# EL_Inverter1.net
KiCad netlist of a schematic drawn in EAGLE
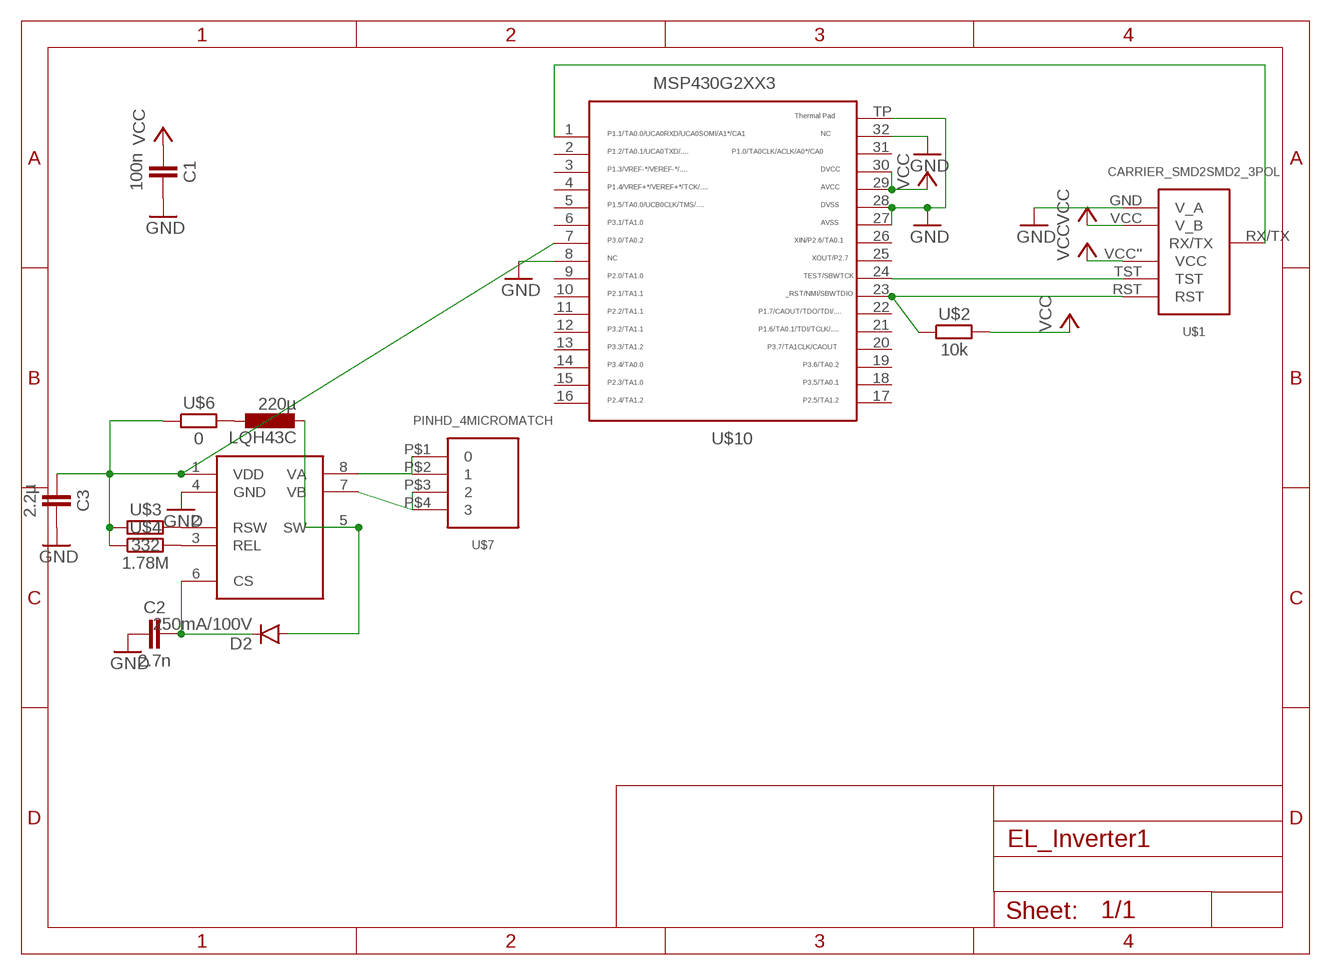
[diagram p0: schematic, sheet 1]

(export (version "E")
  (design (tool "Eeschema 10.0.6"))
  (components
    (comp (ref "C1")
      (value "100n")
      (footprint "eagle-import:603")
      (libsource (lib "eagle-import") (part "CAPACITOR"))
    )
    (comp (ref "C2")
      (value "2.7n")
      (footprint "eagle-import:603")
      (libsource (lib "eagle-import") (part "CAPACITOR"))
    )
    (comp (ref "C3")
      (value "2.2µ")
      (footprint "eagle-import:603")
      (libsource (lib "eagle-import") (part "CAPACITOR"))
    )
    (comp (ref "D2")
      (value "250mA/100V")
      (footprint "eagle-import:SOD-323")
      (libsource (lib "eagle-import") (part "DIODEBAS16"))
    )
    (comp (ref "LQH43C")
      (value "220µ")
      (footprint "eagle-import:L1812")
      (libsource (lib "eagle-import") (part "L-EUL1812"))
    )
    (comp (ref "U$1")
      (value "CARRIER_SMD2SMD2_3POL")
      (footprint "eagle-import:CARRIER_SMD2_3POL")
      (libsource (lib "eagle-import") (part "CARRIER_SMD2SMD2_3POL"))
    )
    (comp (ref "U$2")
      (value "10k")
      (footprint "eagle-import:603")
      (libsource (lib "eagle-import") (part "RESISTOR0603"))
    )
    (comp (ref "U$3")
      (value "332")
      (footprint "eagle-import:603")
      (libsource (lib "eagle-import") (part "RESISTOR0603"))
    )
    (comp (ref "U$4")
      (value "1.78M")
      (footprint "eagle-import:603")
      (libsource (lib "eagle-import") (part "RESISTOR0603"))
    )
    (comp (ref "U$6")
      (value "0")
      (footprint "eagle-import:603")
      (libsource (lib "eagle-import") (part "RESISTOR0603"))
    )
    (comp (ref "U$7")
      (value "PINHD_4MICROMATCH")
      (footprint "eagle-import:MICROMATCH4P0L")
      (libsource (lib "eagle-import") (part "PINHD_4MICROMATCH"))
    )
    (comp (ref "U$8")
      (value "MIC4830")
      (footprint "eagle-import:MSOP8")
      (libsource (lib "eagle-import") (part "MIC4830"))
    )
    (comp (ref "U$10")
      (value "MSP430G2553")
      (footprint "eagle-import:QFN32")
      (libsource (lib "eagle-import") (part "MSP430G2553"))
    )
  )
  (nets
    (net (code "1") (name "GND") (class "Default")
      (node (ref "C1") (pin "2") (pinfunction "2_2") (pintype "passive"))
      (node (ref "C2") (pin "1") (pinfunction "1_1") (pintype "passive"))
      (node (ref "C3") (pin "2") (pinfunction "2_2") (pintype "passive"))
      (node (ref "U$1") (pin "GND") (pinfunction "V_A_GND") (pintype "bidirectional"))
      (node (ref "U$10") (pin "27") (pinfunction "27_27") (pintype "bidirectional"))
      (node (ref "U$10") (pin "28") (pinfunction "28_28") (pintype "bidirectional"))
      (node (ref "U$10") (pin "32") (pinfunction "32_32") (pintype "bidirectional"))
      (node (ref "U$10") (pin "8") (pinfunction "8_8") (pintype "bidirectional"))
      (node (ref "U$10") (pin "TP") (pinfunction "TP_TP") (pintype "bidirectional"))
      (node (ref "U$8") (pin "4") (pinfunction "GND_4") (pintype "bidirectional"))
    )
    (net (code "2") (name "Net-(LQH43C-Pad1)") (class "Default")
      (node (ref "LQH43C") (pin "1") (pinfunction "1_1") (pintype "passive"))
      (node (ref "U$6") (pin "2") (pinfunction "2_2") (pintype "passive"))
    )
    (net (code "3") (name "Net-(U$1-PadRST)") (class "Default")
      (node (ref "U$1") (pin "RST") (pinfunction "RST_RST") (pintype "bidirectional"))
      (node (ref "U$10") (pin "23") (pinfunction "23_23") (pintype "bidirectional"))
      (node (ref "U$2") (pin "1") (pinfunction "1_1") (pintype "passive"))
    )
    (net (code "4") (name "Net-(U$1-PadRX{slash}TX)") (class "Default")
      (node (ref "U$1") (pin "RX/TX") (pinfunction "RX/TX_RX/TX") (pintype "bidirectional"))
      (node (ref "U$10") (pin "1") (pinfunction "1_1") (pintype "bidirectional"))
    )
    (net (code "5") (name "Net-(U$1-PadTST)") (class "Default")
      (node (ref "U$1") (pin "TST") (pinfunction "TST_TST") (pintype "bidirectional"))
      (node (ref "U$10") (pin "24") (pinfunction "24_24") (pintype "bidirectional"))
    )
    (net (code "6") (name "Net-(U$7-0)") (class "Default")
      (node (ref "U$7") (pin "P$1") (pinfunction "0_P$1") (pintype "bidirectional"))
      (node (ref "U$7") (pin "P$2") (pinfunction "1_P$2") (pintype "bidirectional"))
      (node (ref "U$8") (pin "8") (pinfunction "VA_8") (pintype "bidirectional"))
    )
    (net (code "7") (name "Net-(U$7-2)") (class "Default")
      (node (ref "U$7") (pin "P$3") (pinfunction "2_P$3") (pintype "bidirectional"))
      (node (ref "U$7") (pin "P$4") (pinfunction "3_P$4") (pintype "bidirectional"))
      (node (ref "U$8") (pin "7") (pinfunction "VB_7") (pintype "bidirectional"))
    )
    (net (code "8") (name "Net-(U$8-CS)") (class "Default")
      (node (ref "C2") (pin "2") (pinfunction "2_2") (pintype "passive"))
      (node (ref "D2") (pin "C") (pinfunction "C_C") (pintype "passive"))
      (node (ref "U$8") (pin "6") (pinfunction "CS_6") (pintype "bidirectional"))
    )
    (net (code "9") (name "Net-(U$8-REL)") (class "Default")
      (node (ref "U$4") (pin "2") (pinfunction "2_2") (pintype "passive"))
      (node (ref "U$8") (pin "3") (pinfunction "REL_3") (pintype "bidirectional"))
    )
    (net (code "10") (name "Net-(U$8-RSW)") (class "Default")
      (node (ref "U$3") (pin "2") (pinfunction "2_2") (pintype "passive"))
      (node (ref "U$8") (pin "2") (pinfunction "RSW_2") (pintype "bidirectional"))
    )
    (net (code "11") (name "Net-(U$8-SW)") (class "Default")
      (node (ref "D2") (pin "A") (pinfunction "A_A") (pintype "passive"))
      (node (ref "LQH43C") (pin "2") (pinfunction "2_2") (pintype "passive"))
      (node (ref "U$8") (pin "5") (pinfunction "SW_5") (pintype "bidirectional"))
    )
    (net (code "12") (name "Net-(U$8-VDD)") (class "Default")
      (node (ref "C3") (pin "1") (pinfunction "1_1") (pintype "passive"))
      (node (ref "U$10") (pin "7") (pinfunction "7_7") (pintype "bidirectional"))
      (node (ref "U$3") (pin "1") (pinfunction "1_1") (pintype "passive"))
      (node (ref "U$4") (pin "1") (pinfunction "1_1") (pintype "passive"))
      (node (ref "U$6") (pin "1") (pinfunction "1_1") (pintype "passive"))
      (node (ref "U$8") (pin "1") (pinfunction "VDD_1") (pintype "bidirectional"))
    )
    (net (code "13") (name "VCC") (class "Default")
      (node (ref "C1") (pin "1") (pinfunction "1_1") (pintype "passive"))
      (node (ref "U$1") (pin "VCC") (pinfunction "V_B_VCC") (pintype "bidirectional"))
      (node (ref "U$1") (pin "VCC''") (pinfunction "VCC_VCC''") (pintype "bidirectional"))
      (node (ref "U$10") (pin "29") (pinfunction "29_29") (pintype "bidirectional"))
      (node (ref "U$10") (pin "30") (pinfunction "30_30") (pintype "bidirectional"))
      (node (ref "U$2") (pin "2") (pinfunction "2_2") (pintype "passive"))
    )
    (net (code "14") (name "unconnected-(U$10-Pad2)") (class "Default")
      (node (ref "U$10") (pin "2") (pinfunction "2_2") (pintype "bidirectional"))
    )
    (net (code "15") (name "unconnected-(U$10-Pad3)") (class "Default")
      (node (ref "U$10") (pin "3") (pinfunction "3_3") (pintype "bidirectional"))
    )
    (net (code "16") (name "unconnected-(U$10-Pad4)") (class "Default")
      (node (ref "U$10") (pin "4") (pinfunction "4_4") (pintype "bidirectional"))
    )
    (net (code "17") (name "unconnected-(U$10-Pad5)") (class "Default")
      (node (ref "U$10") (pin "5") (pinfunction "5_5") (pintype "bidirectional"))
    )
    (net (code "18") (name "unconnected-(U$10-Pad6)") (class "Default")
      (node (ref "U$10") (pin "6") (pinfunction "6_6") (pintype "bidirectional"))
    )
    (net (code "19") (name "unconnected-(U$10-Pad9)") (class "Default")
      (node (ref "U$10") (pin "9") (pinfunction "9_9") (pintype "bidirectional"))
    )
    (net (code "20") (name "unconnected-(U$10-Pad10)") (class "Default")
      (node (ref "U$10") (pin "10") (pinfunction "10_10") (pintype "bidirectional"))
    )
    (net (code "21") (name "unconnected-(U$10-Pad11)") (class "Default")
      (node (ref "U$10") (pin "11") (pinfunction "11_11") (pintype "bidirectional"))
    )
    (net (code "22") (name "unconnected-(U$10-Pad12)") (class "Default")
      (node (ref "U$10") (pin "12") (pinfunction "12_12") (pintype "bidirectional"))
    )
    (net (code "23") (name "unconnected-(U$10-Pad13)") (class "Default")
      (node (ref "U$10") (pin "13") (pinfunction "13_13") (pintype "bidirectional"))
    )
    (net (code "24") (name "unconnected-(U$10-Pad14)") (class "Default")
      (node (ref "U$10") (pin "14") (pinfunction "14_14") (pintype "bidirectional"))
    )
    (net (code "25") (name "unconnected-(U$10-Pad15)") (class "Default")
      (node (ref "U$10") (pin "15") (pinfunction "15_15") (pintype "bidirectional"))
    )
    (net (code "26") (name "unconnected-(U$10-Pad16)") (class "Default")
      (node (ref "U$10") (pin "16") (pinfunction "16_16") (pintype "bidirectional"))
    )
    (net (code "27") (name "unconnected-(U$10-Pad17)") (class "Default")
      (node (ref "U$10") (pin "17") (pinfunction "17_17") (pintype "bidirectional"))
    )
    (net (code "28") (name "unconnected-(U$10-Pad18)") (class "Default")
      (node (ref "U$10") (pin "18") (pinfunction "18_18") (pintype "bidirectional"))
    )
    (net (code "29") (name "unconnected-(U$10-Pad19)") (class "Default")
      (node (ref "U$10") (pin "19") (pinfunction "19_19") (pintype "bidirectional"))
    )
    (net (code "30") (name "unconnected-(U$10-Pad20)") (class "Default")
      (node (ref "U$10") (pin "20") (pinfunction "20_20") (pintype "bidirectional"))
    )
    (net (code "31") (name "unconnected-(U$10-Pad21)") (class "Default")
      (node (ref "U$10") (pin "21") (pinfunction "21_21") (pintype "bidirectional"))
    )
    (net (code "32") (name "unconnected-(U$10-Pad22)") (class "Default")
      (node (ref "U$10") (pin "22") (pinfunction "22_22") (pintype "bidirectional"))
    )
    (net (code "33") (name "unconnected-(U$10-Pad25)") (class "Default")
      (node (ref "U$10") (pin "25") (pinfunction "25_25") (pintype "bidirectional"))
    )
    (net (code "34") (name "unconnected-(U$10-Pad26)") (class "Default")
      (node (ref "U$10") (pin "26") (pinfunction "26_26") (pintype "bidirectional"))
    )
    (net (code "35") (name "unconnected-(U$10-Pad31)") (class "Default")
      (node (ref "U$10") (pin "31") (pinfunction "31_31") (pintype "bidirectional"))
    )
  )
)
